# BATTERIES_CONTROLLER__V3.net
KiCad netlist of a schematic drawn in EAGLE
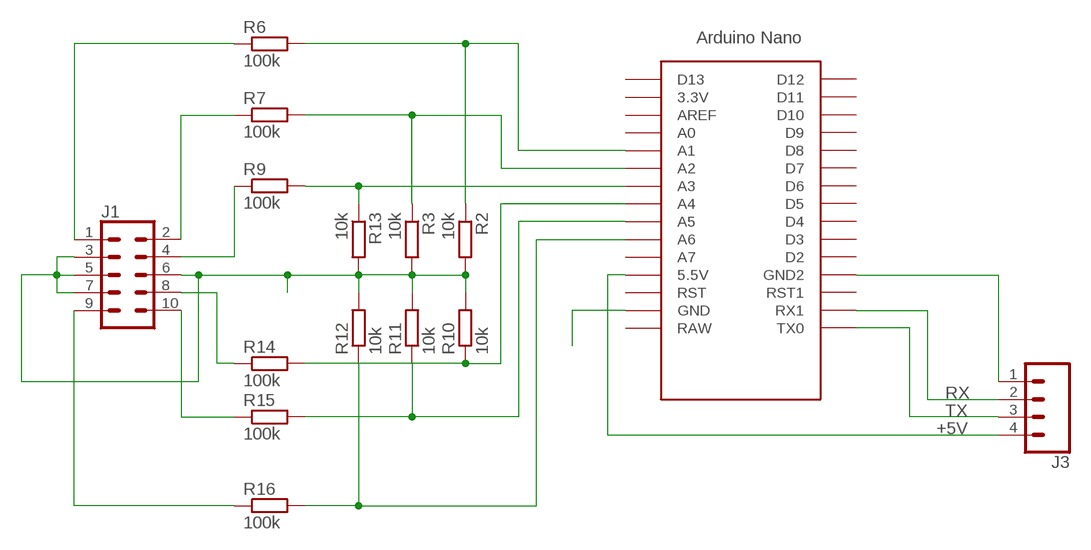
[diagram p0: schematic, sheet 1]

(export (version "E")
  (design (tool "Eeschema 10.0.6"))
  (components
    (comp (ref "J1")
      (value "CONN_05X2SHD")
      (footprint "eagle-import:2X5-SHROUDED")
      (libsource (lib "eagle-import") (part "CONN_05X2SHD"))
    )
    (comp (ref "J3")
      (value "CONN_04")
      (footprint "eagle-import:1X04")
      (libsource (lib "eagle-import") (part "CONN_04"))
    )
    (comp (ref "R2")
      (value "10k")
      (footprint "eagle-import:M0805")
      (libsource (lib "eagle-import") (part "R-EU_M0805"))
    )
    (comp (ref "R3")
      (value "10k")
      (footprint "eagle-import:M0805")
      (libsource (lib "eagle-import") (part "R-EU_M0805"))
    )
    (comp (ref "R6")
      (value "100k")
      (footprint "eagle-import:M0805")
      (libsource (lib "eagle-import") (part "R-EU_M0805"))
    )
    (comp (ref "R7")
      (value "100k")
      (footprint "eagle-import:M0805")
      (libsource (lib "eagle-import") (part "R-EU_M0805"))
    )
    (comp (ref "R9")
      (value "100k")
      (footprint "eagle-import:M0805")
      (libsource (lib "eagle-import") (part "R-EU_M0805"))
    )
    (comp (ref "R10")
      (value "10k")
      (footprint "eagle-import:M0805")
      (libsource (lib "eagle-import") (part "R-EU_M0805"))
    )
    (comp (ref "R11")
      (value "10k")
      (footprint "eagle-import:M0805")
      (libsource (lib "eagle-import") (part "R-EU_M0805"))
    )
    (comp (ref "R12")
      (value "10k")
      (footprint "eagle-import:M0805")
      (libsource (lib "eagle-import") (part "R-EU_M0805"))
    )
    (comp (ref "R13")
      (value "10k")
      (footprint "eagle-import:M0805")
      (libsource (lib "eagle-import") (part "R-EU_M0805"))
    )
    (comp (ref "R14")
      (value "100k")
      (footprint "eagle-import:M0805")
      (libsource (lib "eagle-import") (part "R-EU_M0805"))
    )
    (comp (ref "R15")
      (value "100k")
      (footprint "eagle-import:M0805")
      (libsource (lib "eagle-import") (part "R-EU_M0805"))
    )
    (comp (ref "R16")
      (value "100k")
      (footprint "eagle-import:M0805")
      (libsource (lib "eagle-import") (part "R-EU_M0805"))
    )
    (comp (ref "U$1")
      (value "NANO")
      (footprint "eagle-import:NANO")
      (libsource (lib "eagle-import") (part "NANO"))
    )
  )
  (nets
    (net (code "1") (name "/+5V") (class "Default")
      (node (ref "J3") (pin "4") (pinfunction "4_4") (pintype "passive"))
      (node (ref "U$1") (pin "5V") (pinfunction "5.5V_5V") (pintype "bidirectional"))
    )
    (net (code "2") (name "/RX") (class "Default")
      (node (ref "J3") (pin "2") (pinfunction "2_2") (pintype "passive"))
      (node (ref "U$1") (pin "RX1") (pinfunction "RX1_RX1") (pintype "bidirectional"))
    )
    (net (code "3") (name "/TX") (class "Default")
      (node (ref "J3") (pin "3") (pinfunction "3_3") (pintype "passive"))
      (node (ref "U$1") (pin "TX0") (pinfunction "TX0_TX0") (pintype "bidirectional"))
    )
    (net (code "4") (name "Net-(J1-Pad1)") (class "Default")
      (node (ref "J1") (pin "1") (pinfunction "1_1") (pintype "passive"))
      (node (ref "R6") (pin "1") (pinfunction "1_1") (pintype "passive"))
    )
    (net (code "5") (name "Net-(J1-Pad2)") (class "Default")
      (node (ref "J1") (pin "2") (pinfunction "2_2") (pintype "passive"))
      (node (ref "R7") (pin "1") (pinfunction "1_1") (pintype "passive"))
    )
    (net (code "6") (name "Net-(J1-Pad3)") (class "Default")
      (node (ref "J1") (pin "3") (pinfunction "3_3") (pintype "passive"))
      (node (ref "J1") (pin "5") (pinfunction "5_5") (pintype "passive"))
      (node (ref "J1") (pin "6") (pinfunction "6_6") (pintype "passive"))
      (node (ref "J1") (pin "7") (pinfunction "7_7") (pintype "passive"))
      (node (ref "R10") (pin "2") (pinfunction "2_2") (pintype "passive"))
      (node (ref "R11") (pin "2") (pinfunction "2_2") (pintype "passive"))
      (node (ref "R12") (pin "2") (pinfunction "2_2") (pintype "passive"))
      (node (ref "R13") (pin "2") (pinfunction "2_2") (pintype "passive"))
      (node (ref "R2") (pin "2") (pinfunction "2_2") (pintype "passive"))
      (node (ref "R3") (pin "2") (pinfunction "2_2") (pintype "passive"))
    )
    (net (code "7") (name "Net-(J1-Pad4)") (class "Default")
      (node (ref "J1") (pin "4") (pinfunction "4_4") (pintype "passive"))
      (node (ref "R9") (pin "1") (pinfunction "1_1") (pintype "passive"))
    )
    (net (code "8") (name "Net-(J1-Pad8)") (class "Default")
      (node (ref "J1") (pin "8") (pinfunction "8_8") (pintype "passive"))
      (node (ref "R14") (pin "1") (pinfunction "1_1") (pintype "passive"))
    )
    (net (code "9") (name "Net-(J1-Pad9)") (class "Default")
      (node (ref "J1") (pin "9") (pinfunction "9_9") (pintype "passive"))
      (node (ref "R16") (pin "1") (pinfunction "1_1") (pintype "passive"))
    )
    (net (code "10") (name "Net-(J1-Pad10)") (class "Default")
      (node (ref "J1") (pin "10") (pinfunction "10_10") (pintype "passive"))
      (node (ref "R15") (pin "1") (pinfunction "1_1") (pintype "passive"))
    )
    (net (code "11") (name "Net-(R2-Pad1)") (class "Default")
      (node (ref "R2") (pin "1") (pinfunction "1_1") (pintype "passive"))
      (node (ref "R6") (pin "2") (pinfunction "2_2") (pintype "passive"))
      (node (ref "U$1") (pin "A1") (pinfunction "A1_A1") (pintype "bidirectional"))
    )
    (net (code "12") (name "Net-(R3-Pad1)") (class "Default")
      (node (ref "R3") (pin "1") (pinfunction "1_1") (pintype "passive"))
      (node (ref "R7") (pin "2") (pinfunction "2_2") (pintype "passive"))
      (node (ref "U$1") (pin "A2") (pinfunction "A2_A2") (pintype "bidirectional"))
    )
    (net (code "13") (name "Net-(R10-Pad1)") (class "Default")
      (node (ref "R10") (pin "1") (pinfunction "1_1") (pintype "passive"))
      (node (ref "R14") (pin "2") (pinfunction "2_2") (pintype "passive"))
      (node (ref "U$1") (pin "A4") (pinfunction "A4_A4") (pintype "bidirectional"))
    )
    (net (code "14") (name "Net-(R11-Pad1)") (class "Default")
      (node (ref "R11") (pin "1") (pinfunction "1_1") (pintype "passive"))
      (node (ref "R15") (pin "2") (pinfunction "2_2") (pintype "passive"))
      (node (ref "U$1") (pin "A5") (pinfunction "A5_A5") (pintype "bidirectional"))
    )
    (net (code "15") (name "Net-(R12-Pad1)") (class "Default")
      (node (ref "R12") (pin "1") (pinfunction "1_1") (pintype "passive"))
      (node (ref "R16") (pin "2") (pinfunction "2_2") (pintype "passive"))
      (node (ref "U$1") (pin "A6") (pinfunction "A6_A6") (pintype "bidirectional"))
    )
    (net (code "16") (name "Net-(R13-Pad1)") (class "Default")
      (node (ref "R13") (pin "1") (pinfunction "1_1") (pintype "passive"))
      (node (ref "R9") (pin "2") (pinfunction "2_2") (pintype "passive"))
      (node (ref "U$1") (pin "A3") (pinfunction "A3_A3") (pintype "bidirectional"))
    )
    (net (code "17") (name "Net-(U$1-GND2)") (class "Default")
      (node (ref "J3") (pin "1") (pinfunction "1_1") (pintype "passive"))
      (node (ref "U$1") (pin "GND1") (pinfunction "GND2_GND1") (pintype "bidirectional"))
    )
    (net (code "18") (name "unconnected-(U$1-Pad3.3V)") (class "Default")
      (node (ref "U$1") (pin "3.3V") (pinfunction "3.3V_3.3V") (pintype "bidirectional"))
    )
    (net (code "19") (name "unconnected-(U$1-PadA0)") (class "Default")
      (node (ref "U$1") (pin "A0") (pinfunction "A0_A0") (pintype "bidirectional"))
    )
    (net (code "20") (name "unconnected-(U$1-PadA7)") (class "Default")
      (node (ref "U$1") (pin "A7") (pinfunction "A7_A7") (pintype "bidirectional"))
    )
    (net (code "21") (name "unconnected-(U$1-PadAREF)") (class "Default")
      (node (ref "U$1") (pin "AREF") (pinfunction "AREF_AREF") (pintype "bidirectional"))
    )
    (net (code "22") (name "unconnected-(U$1-PadD2)") (class "Default")
      (node (ref "U$1") (pin "D2") (pinfunction "D2_D2") (pintype "bidirectional"))
    )
    (net (code "23") (name "unconnected-(U$1-PadD3)") (class "Default")
      (node (ref "U$1") (pin "D3") (pinfunction "D3_D3") (pintype "bidirectional"))
    )
    (net (code "24") (name "unconnected-(U$1-PadD4)") (class "Default")
      (node (ref "U$1") (pin "D4") (pinfunction "D4_D4") (pintype "bidirectional"))
    )
    (net (code "25") (name "unconnected-(U$1-PadD5)") (class "Default")
      (node (ref "U$1") (pin "D5") (pinfunction "D5_D5") (pintype "bidirectional"))
    )
    (net (code "26") (name "unconnected-(U$1-PadD6)") (class "Default")
      (node (ref "U$1") (pin "D6") (pinfunction "D6_D6") (pintype "bidirectional"))
    )
    (net (code "27") (name "unconnected-(U$1-PadD7)") (class "Default")
      (node (ref "U$1") (pin "D7") (pinfunction "D7_D7") (pintype "bidirectional"))
    )
    (net (code "28") (name "unconnected-(U$1-PadD8)") (class "Default")
      (node (ref "U$1") (pin "D8") (pinfunction "D8_D8") (pintype "bidirectional"))
    )
    (net (code "29") (name "unconnected-(U$1-PadD9)") (class "Default")
      (node (ref "U$1") (pin "D9") (pinfunction "D9_D9") (pintype "bidirectional"))
    )
    (net (code "30") (name "unconnected-(U$1-PadD10)") (class "Default")
      (node (ref "U$1") (pin "D10") (pinfunction "D10_D10") (pintype "bidirectional"))
    )
    (net (code "31") (name "unconnected-(U$1-PadD11)") (class "Default")
      (node (ref "U$1") (pin "D11") (pinfunction "D11_D11") (pintype "bidirectional"))
    )
    (net (code "32") (name "unconnected-(U$1-PadD12)") (class "Default")
      (node (ref "U$1") (pin "D12") (pinfunction "D12_D12") (pintype "bidirectional"))
    )
    (net (code "33") (name "unconnected-(U$1-PadD13)") (class "Default")
      (node (ref "U$1") (pin "D13") (pinfunction "D13_D13") (pintype "bidirectional"))
    )
    (net (code "34") (name "unconnected-(U$1-PadGND)") (class "Default")
      (node (ref "U$1") (pin "GND") (pinfunction "GND_GND") (pintype "bidirectional"))
    )
    (net (code "35") (name "unconnected-(U$1-PadICSP1)") (class "Default")
      (node (ref "U$1") (pin "ICSP1") (pinfunction "ICSP1_ICSP1") (pintype "bidirectional"))
    )
    (net (code "36") (name "unconnected-(U$1-PadICSP2)") (class "Default")
      (node (ref "U$1") (pin "ICSP2") (pinfunction "ICSP2_ICSP2") (pintype "bidirectional"))
    )
    (net (code "37") (name "unconnected-(U$1-PadICSP3)") (class "Default")
      (node (ref "U$1") (pin "ICSP3") (pinfunction "ICSP3_ICSP3") (pintype "bidirectional"))
    )
    (net (code "38") (name "unconnected-(U$1-PadICSP4)") (class "Default")
      (node (ref "U$1") (pin "ICSP4") (pinfunction "ICSP4_ICSP4") (pintype "bidirectional"))
    )
    (net (code "39") (name "unconnected-(U$1-PadICSP5)") (class "Default")
      (node (ref "U$1") (pin "ICSP5") (pinfunction "ICSP5_ICSP5") (pintype "bidirectional"))
    )
    (net (code "40") (name "unconnected-(U$1-PadICSP6)") (class "Default")
      (node (ref "U$1") (pin "ICSP6") (pinfunction "ICSP6_ICSP6") (pintype "bidirectional"))
    )
    (net (code "41") (name "unconnected-(U$1-PadRAW)") (class "Default")
      (node (ref "U$1") (pin "RAW") (pinfunction "RAW_RAW") (pintype "bidirectional"))
    )
    (net (code "42") (name "unconnected-(U$1-PadRST)") (class "Default")
      (node (ref "U$1") (pin "RST") (pinfunction "RST_RST") (pintype "bidirectional"))
    )
    (net (code "43") (name "unconnected-(U$1-PadRST1)") (class "Default")
      (node (ref "U$1") (pin "RST1") (pinfunction "RST1_RST1") (pintype "bidirectional"))
    )
  )
)
